# IR_Recever_Card.net
KiCad netlist of a schematic drawn in EAGLE
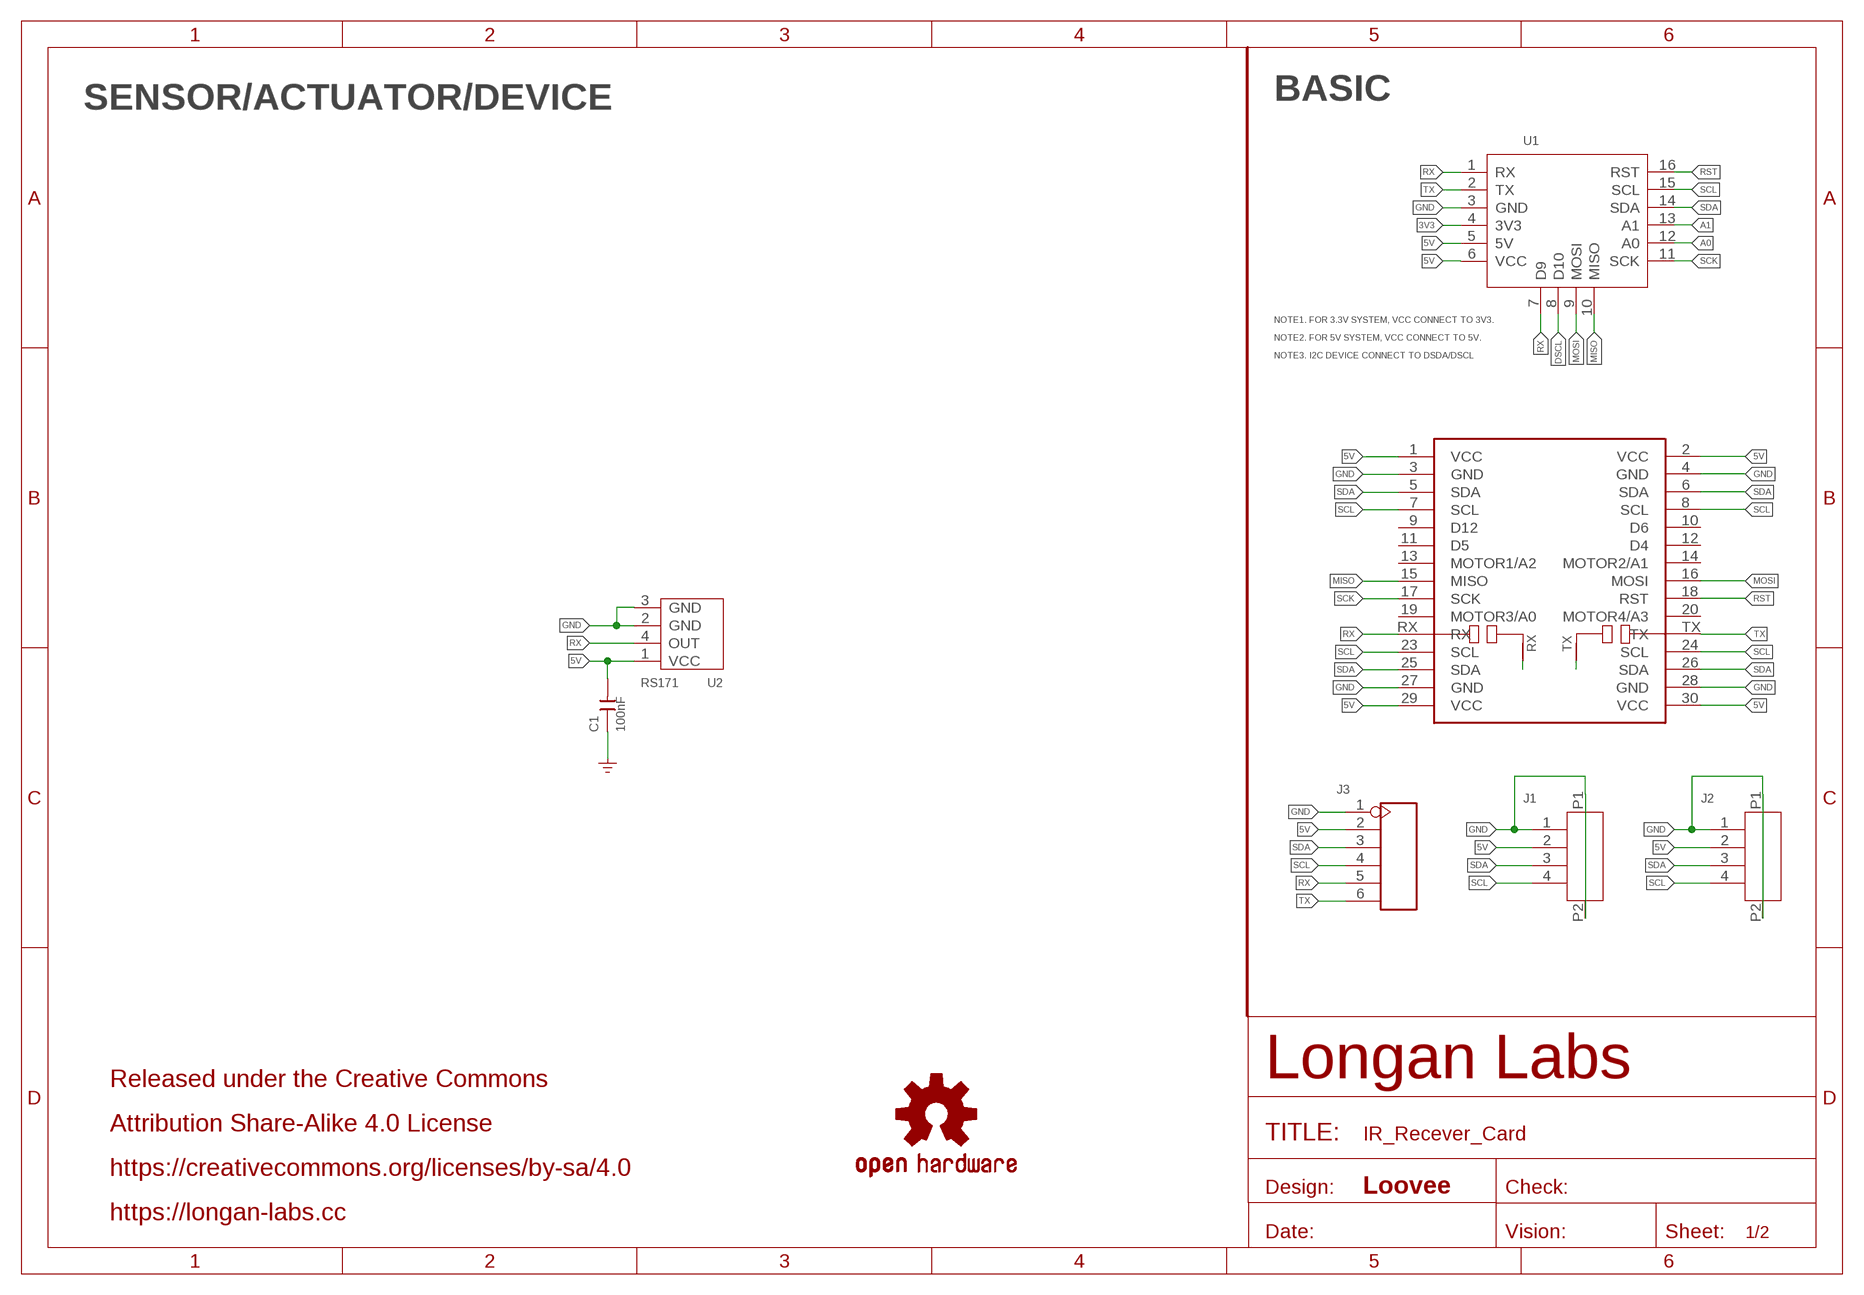
[diagram p0: schematic, sheet 1]

(export (version "E")
  (design (tool "Eeschema 10.0.6"))
  (components
    (comp (ref "C1")
      (value "100nF")
      (footprint "eagle-import:C0603")
      (libsource (lib "eagle-import") (part "CAP-0603"))
    )
    (comp (ref "J1")
      (value "HEADER-4P-1.0")
      (footprint "eagle-import:4P-1.0-90D")
      (libsource (lib "eagle-import") (part "HEADER-4P-1.0"))
    )
    (comp (ref "J2")
      (value "HEADER-4P-1.0")
      (footprint "eagle-import:4P-1.0-90D")
      (libsource (lib "eagle-import") (part "HEADER-4P-1.0"))
    )
    (comp (ref "J3")
      (value "HEADER-6P-55/35MIL")
      (footprint "eagle-import:H6-2.54")
      (libsource (lib "eagle-import") (part "HEADER-6P-55/35MIL"))
    )
    (comp (ref "LOGO2")
      (value "OSHW-LOGOS")
      (footprint "eagle-import:OSHW-LOGO-S")
      (libsource (lib "eagle-import") (part "OSHW-LOGOS"))
    )
    (comp (ref "MOUDLE1")
      (value "MOUDLE-CARDS-UART'BOARD'")
      (footprint "eagle-import:MOUDLE-2X15P-UART")
      (libsource (lib "eagle-import") (part "MOUDLE-CARDS-UART'BOARD'"))
    )
    (comp (ref "U1")
      (value "MOUDLE-CARDS")
      (footprint "eagle-import:16P-2.0-CARDS")
      (libsource (lib "eagle-import") (part "MOUDLE-CARDS"))
    )
    (comp (ref "U2")
      (value "RS171")
      (footprint "eagle-import:4P-SMD-L7.6_W5.75MM")
      (libsource (lib "eagle-import") (part "RS-171"))
    )
  )
  (nets
    (net (code "1") (name "3V3") (class "Default")
      (node (ref "U1") (pin "4") (pinfunction "3V3_4") (pintype "bidirectional"))
    )
    (net (code "2") (name "5V") (class "Default")
      (node (ref "C1") (pin "2") (pinfunction "2_2") (pintype "passive"))
      (node (ref "J1") (pin "2") (pinfunction "2_2") (pintype "bidirectional"))
      (node (ref "J2") (pin "2") (pinfunction "2_2") (pintype "bidirectional"))
      (node (ref "J3") (pin "2") (pinfunction "2_2") (pintype "bidirectional"))
      (node (ref "MOUDLE1") (pin "1") (pinfunction "VCC_1") (pintype "bidirectional"))
      (node (ref "MOUDLE1") (pin "2") (pinfunction "VCC_2") (pintype "bidirectional"))
      (node (ref "MOUDLE1") (pin "29") (pinfunction "VCC_29") (pintype "bidirectional"))
      (node (ref "MOUDLE1") (pin "30") (pinfunction "VCC_30") (pintype "bidirectional"))
      (node (ref "U1") (pin "5") (pinfunction "5V_5") (pintype "bidirectional"))
      (node (ref "U1") (pin "6") (pinfunction "VCC_6") (pintype "bidirectional"))
      (node (ref "U2") (pin "1") (pinfunction "VCC_1") (pintype "bidirectional"))
    )
    (net (code "3") (name "A0") (class "Default")
      (node (ref "U1") (pin "12") (pinfunction "A0_12") (pintype "bidirectional"))
    )
    (net (code "4") (name "A1") (class "Default")
      (node (ref "U1") (pin "13") (pinfunction "A1_13") (pintype "bidirectional"))
    )
    (net (code "5") (name "DSCL") (class "Default")
      (node (ref "U1") (pin "8") (pinfunction "D10_8") (pintype "bidirectional"))
    )
    (net (code "6") (name "GND") (class "Default")
      (node (ref "C1") (pin "1") (pinfunction "1_1") (pintype "passive"))
      (node (ref "J1") (pin "1") (pinfunction "1_1") (pintype "bidirectional"))
      (node (ref "J1") (pin "P1") (pinfunction "P1_P1") (pintype "bidirectional"))
      (node (ref "J1") (pin "P2") (pinfunction "P2_P2") (pintype "bidirectional"))
      (node (ref "J2") (pin "1") (pinfunction "1_1") (pintype "bidirectional"))
      (node (ref "J2") (pin "P1") (pinfunction "P1_P1") (pintype "bidirectional"))
      (node (ref "J2") (pin "P2") (pinfunction "P2_P2") (pintype "bidirectional"))
      (node (ref "J3") (pin "1") (pinfunction "1_1") (pintype "bidirectional"))
      (node (ref "MOUDLE1") (pin "27") (pinfunction "GND_27") (pintype "bidirectional"))
      (node (ref "MOUDLE1") (pin "28") (pinfunction "GND_28") (pintype "bidirectional"))
      (node (ref "MOUDLE1") (pin "3") (pinfunction "GND_3") (pintype "bidirectional"))
      (node (ref "MOUDLE1") (pin "4") (pinfunction "GND_4") (pintype "bidirectional"))
      (node (ref "U1") (pin "3") (pinfunction "GND_3") (pintype "bidirectional"))
      (node (ref "U2") (pin "2") (pinfunction "GND_2") (pintype "bidirectional"))
      (node (ref "U2") (pin "3") (pinfunction "GND_3") (pintype "bidirectional"))
    )
    (net (code "7") (name "MISO") (class "Default")
      (node (ref "MOUDLE1") (pin "15") (pinfunction "MISO_15") (pintype "bidirectional"))
      (node (ref "U1") (pin "10") (pinfunction "MISO_10") (pintype "bidirectional"))
    )
    (net (code "8") (name "MOSI") (class "Default")
      (node (ref "MOUDLE1") (pin "16") (pinfunction "MOSI_16") (pintype "bidirectional"))
      (node (ref "U1") (pin "9") (pinfunction "MOSI_9") (pintype "bidirectional"))
    )
    (net (code "9") (name "Net-(MOUDLE1-RX{slash}N-PadRX{slash}N1)") (class "Default")
      (node (ref "MOUDLE1") (pin "RX/N1") (pinfunction "RX/N_RX/N1") (pintype "bidirectional"))
      (node (ref "MOUDLE1") (pin "RX/N2") (pinfunction "RX/N_RX/N2") (pintype "bidirectional"))
    )
    (net (code "10") (name "Net-(MOUDLE1-TX{slash}N-PadTX{slash}N1)") (class "Default")
      (node (ref "MOUDLE1") (pin "TX/N1") (pinfunction "TX/N_TX/N1") (pintype "bidirectional"))
      (node (ref "MOUDLE1") (pin "TX/N2") (pinfunction "TX/N_TX/N2") (pintype "bidirectional"))
    )
    (net (code "11") (name "RST") (class "Default")
      (node (ref "MOUDLE1") (pin "18") (pinfunction "RST_18") (pintype "bidirectional"))
      (node (ref "U1") (pin "16") (pinfunction "RST_16") (pintype "bidirectional"))
    )
    (net (code "12") (name "RX") (class "Default")
      (node (ref "J3") (pin "5") (pinfunction "5_5") (pintype "bidirectional"))
      (node (ref "MOUDLE1") (pin "RX") (pinfunction "RX_RX") (pintype "bidirectional"))
      (node (ref "U1") (pin "1") (pinfunction "RX_1") (pintype "bidirectional"))
      (node (ref "U1") (pin "7") (pinfunction "D9_7") (pintype "bidirectional"))
      (node (ref "U2") (pin "4") (pinfunction "OUT_4") (pintype "bidirectional"))
    )
    (net (code "13") (name "SCK") (class "Default")
      (node (ref "MOUDLE1") (pin "17") (pinfunction "SCK_17") (pintype "bidirectional"))
      (node (ref "U1") (pin "11") (pinfunction "SCK_11") (pintype "bidirectional"))
    )
    (net (code "14") (name "SCL") (class "Default")
      (node (ref "J1") (pin "4") (pinfunction "4_4") (pintype "bidirectional"))
      (node (ref "J2") (pin "4") (pinfunction "4_4") (pintype "bidirectional"))
      (node (ref "J3") (pin "4") (pinfunction "4_4") (pintype "bidirectional"))
      (node (ref "MOUDLE1") (pin "23") (pinfunction "SCL_23") (pintype "bidirectional"))
      (node (ref "MOUDLE1") (pin "24") (pinfunction "SCL_24") (pintype "bidirectional"))
      (node (ref "MOUDLE1") (pin "7") (pinfunction "SCL_7") (pintype "bidirectional"))
      (node (ref "MOUDLE1") (pin "8") (pinfunction "SCL_8") (pintype "bidirectional"))
      (node (ref "U1") (pin "15") (pinfunction "SCL_15") (pintype "bidirectional"))
    )
    (net (code "15") (name "SDA") (class "Default")
      (node (ref "J1") (pin "3") (pinfunction "3_3") (pintype "bidirectional"))
      (node (ref "J2") (pin "3") (pinfunction "3_3") (pintype "bidirectional"))
      (node (ref "J3") (pin "3") (pinfunction "3_3") (pintype "bidirectional"))
      (node (ref "MOUDLE1") (pin "25") (pinfunction "SDA_25") (pintype "bidirectional"))
      (node (ref "MOUDLE1") (pin "26") (pinfunction "SDA_26") (pintype "bidirectional"))
      (node (ref "MOUDLE1") (pin "5") (pinfunction "SDA_5") (pintype "bidirectional"))
      (node (ref "MOUDLE1") (pin "6") (pinfunction "SDA_6") (pintype "bidirectional"))
      (node (ref "U1") (pin "14") (pinfunction "SDA_14") (pintype "bidirectional"))
    )
    (net (code "16") (name "TX") (class "Default")
      (node (ref "J3") (pin "6") (pinfunction "6_6") (pintype "bidirectional"))
      (node (ref "MOUDLE1") (pin "TX") (pinfunction "TX_TX") (pintype "bidirectional"))
      (node (ref "U1") (pin "2") (pinfunction "TX_2") (pintype "bidirectional"))
    )
    (net (code "17") (name "unconnected-(MOUDLE1-D4-Pad12)") (class "Default")
      (node (ref "MOUDLE1") (pin "12") (pinfunction "D4_12") (pintype "bidirectional"))
    )
    (net (code "18") (name "unconnected-(MOUDLE1-D5-Pad11)") (class "Default")
      (node (ref "MOUDLE1") (pin "11") (pinfunction "D5_11") (pintype "bidirectional"))
    )
    (net (code "19") (name "unconnected-(MOUDLE1-D6-Pad10)") (class "Default")
      (node (ref "MOUDLE1") (pin "10") (pinfunction "D6_10") (pintype "bidirectional"))
    )
    (net (code "20") (name "unconnected-(MOUDLE1-D12-Pad9)") (class "Default")
      (node (ref "MOUDLE1") (pin "9") (pinfunction "D12_9") (pintype "bidirectional"))
    )
    (net (code "21") (name "unconnected-(MOUDLE1-MOTOR1{slash}A2-Pad13)") (class "Default")
      (node (ref "MOUDLE1") (pin "13") (pinfunction "MOTOR1/A2_13") (pintype "bidirectional"))
    )
    (net (code "22") (name "unconnected-(MOUDLE1-MOTOR2{slash}A1-Pad14)") (class "Default")
      (node (ref "MOUDLE1") (pin "14") (pinfunction "MOTOR2/A1_14") (pintype "bidirectional"))
    )
    (net (code "23") (name "unconnected-(MOUDLE1-MOTOR3{slash}A0-Pad19)") (class "Default")
      (node (ref "MOUDLE1") (pin "19") (pinfunction "MOTOR3/A0_19") (pintype "bidirectional"))
    )
    (net (code "24") (name "unconnected-(MOUDLE1-MOTOR4{slash}A3-Pad20)") (class "Default")
      (node (ref "MOUDLE1") (pin "20") (pinfunction "MOTOR4/A3_20") (pintype "bidirectional"))
    )
  )
)
